# leddriver2X3.net
KiCad netlist of a schematic drawn in EAGLE
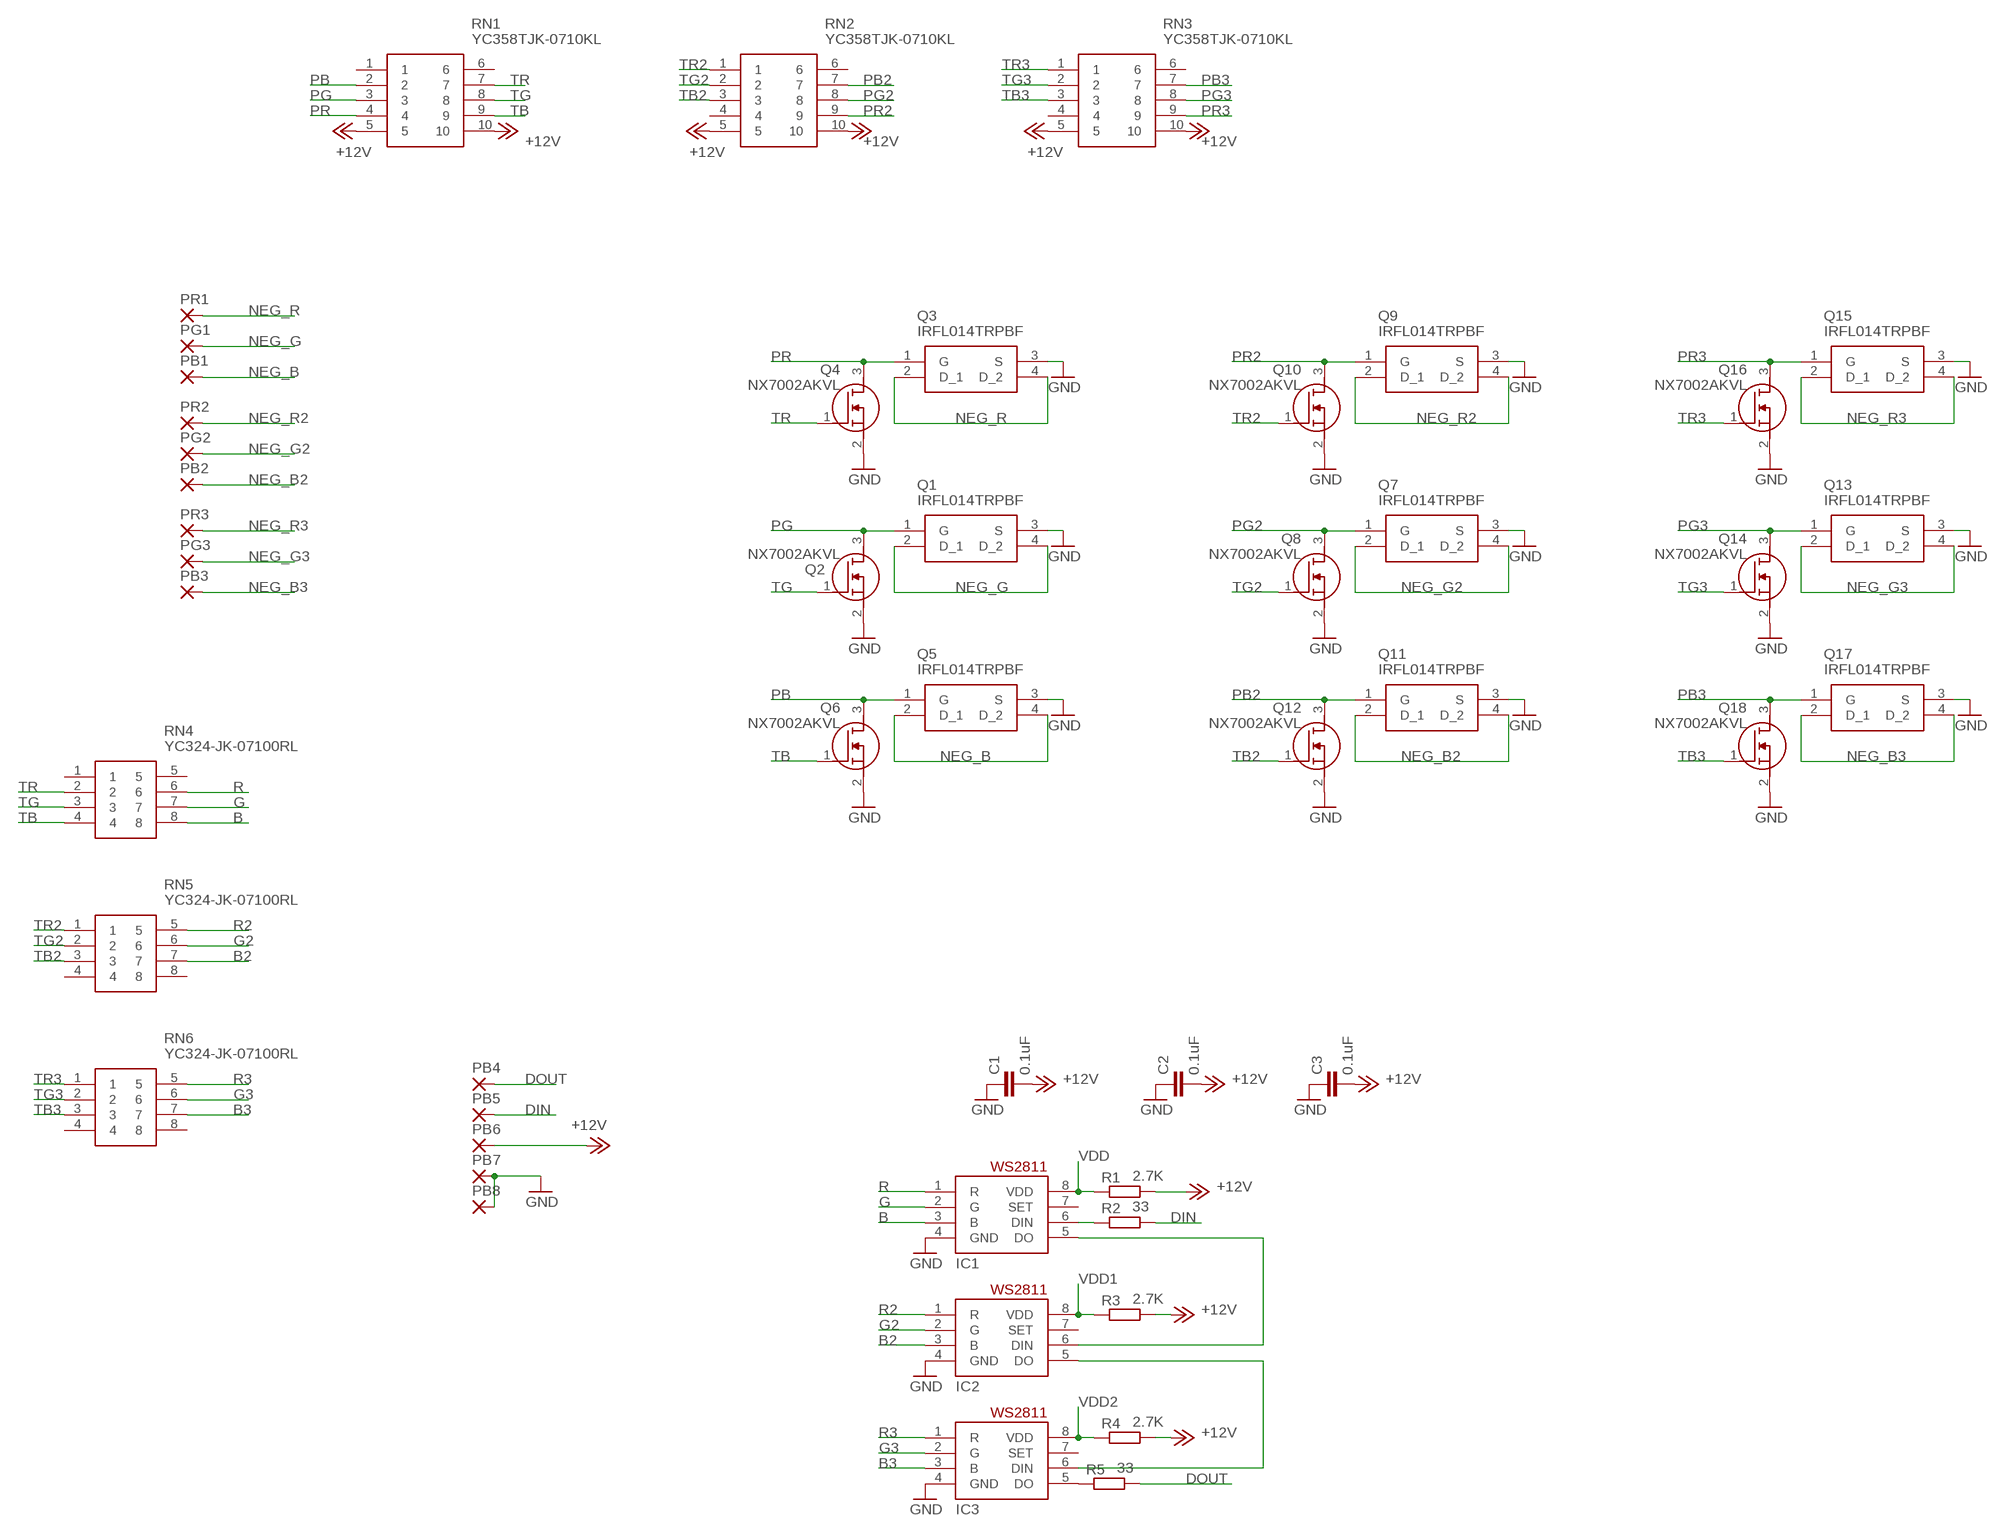
[diagram p0: schematic, sheet 1]

(export (version "E")
  (design (tool "Eeschema 10.0.6"))
  (components
    (comp (ref "C1")
      (value "0.1uF")
      (footprint "eagle-import:C1206")
      (libsource (lib "eagle-import") (part "C-EUC1206"))
    )
    (comp (ref "C2")
      (value "0.1uF")
      (footprint "eagle-import:C1206")
      (libsource (lib "eagle-import") (part "C-EUC1206"))
    )
    (comp (ref "C3")
      (value "0.1uF")
      (footprint "eagle-import:C1206")
      (libsource (lib "eagle-import") (part "C-EUC1206"))
    )
    (comp (ref "IC1")
      (value "WS2811-SOP8")
      (footprint "eagle-import:SO08-SKINNYPADS")
      (libsource (lib "eagle-import") (part "WS2811-SOP8"))
    )
    (comp (ref "IC2")
      (value "WS2811-SOP8")
      (footprint "eagle-import:SO08-SKINNYPADS")
      (libsource (lib "eagle-import") (part "WS2811-SOP8"))
    )
    (comp (ref "IC3")
      (value "WS2811-SOP8")
      (footprint "eagle-import:SO08-SKINNYPADS")
      (libsource (lib "eagle-import") (part "WS2811-SOP8"))
    )
    (comp (ref "PB1")
      (value "3,81/1,4")
      (footprint "eagle-import:3,81_1,4")
      (libsource (lib "eagle-import") (part "3,81/1,4"))
    )
    (comp (ref "PB2")
      (value "3,81/1,4")
      (footprint "eagle-import:3,81_1,4")
      (libsource (lib "eagle-import") (part "3,81/1,4"))
    )
    (comp (ref "PB3")
      (value "3,81/1,4")
      (footprint "eagle-import:3,81_1,4")
      (libsource (lib "eagle-import") (part "3,81/1,4"))
    )
    (comp (ref "PB4")
      (value "3,81/1,4")
      (footprint "eagle-import:3,81_1,4")
      (libsource (lib "eagle-import") (part "3,81/1,4"))
    )
    (comp (ref "PB5")
      (value "3,81/1,4")
      (footprint "eagle-import:3,81_1,4")
      (libsource (lib "eagle-import") (part "3,81/1,4"))
    )
    (comp (ref "PB6")
      (value "3,81/1,4")
      (footprint "eagle-import:3,81_1,4")
      (libsource (lib "eagle-import") (part "3,81/1,4"))
    )
    (comp (ref "PB7")
      (value "3,81/1,4")
      (footprint "eagle-import:3,81_1,4")
      (libsource (lib "eagle-import") (part "3,81/1,4"))
    )
    (comp (ref "PB8")
      (value "3,81/1,4")
      (footprint "eagle-import:3,81_1,4")
      (libsource (lib "eagle-import") (part "3,81/1,4"))
    )
    (comp (ref "PG1")
      (value "3,81/1,4")
      (footprint "eagle-import:3,81_1,4")
      (libsource (lib "eagle-import") (part "3,81/1,4"))
    )
    (comp (ref "PG2")
      (value "3,81/1,4")
      (footprint "eagle-import:3,81_1,4")
      (libsource (lib "eagle-import") (part "3,81/1,4"))
    )
    (comp (ref "PG3")
      (value "3,81/1,4")
      (footprint "eagle-import:3,81_1,4")
      (libsource (lib "eagle-import") (part "3,81/1,4"))
    )
    (comp (ref "PR1")
      (value "3,81/1,4")
      (footprint "eagle-import:3,81_1,4")
      (libsource (lib "eagle-import") (part "3,81/1,4"))
    )
    (comp (ref "PR2")
      (value "3,81/1,4")
      (footprint "eagle-import:3,81_1,4")
      (libsource (lib "eagle-import") (part "3,81/1,4"))
    )
    (comp (ref "PR3")
      (value "3,81/1,4")
      (footprint "eagle-import:3,81_1,4")
      (libsource (lib "eagle-import") (part "3,81/1,4"))
    )
    (comp (ref "Q1")
      (value "IRFL014TRPBF")
      (footprint "eagle-import:SOT230P700X180-4N")
      (fields (field (name "MOUSER_PART_NUMBER") "844-IRFL014TRPBF"))
      (libsource (lib "eagle-import") (part "IRFL014TRPBF"))
    )
    (comp (ref "Q2")
      (value "NX7002AKVL")
      (footprint "eagle-import:SOT95P230X110-3N")
      (fields (field (name "MOUSER_PART_NUMBER") "771-NX7002AKVL"))
      (libsource (lib "eagle-import") (part "NX7002AKVL"))
    )
    (comp (ref "Q3")
      (value "IRFL014TRPBF")
      (footprint "eagle-import:SOT230P700X180-4N")
      (fields (field (name "MOUSER_PART_NUMBER") "844-IRFL014TRPBF"))
      (libsource (lib "eagle-import") (part "IRFL014TRPBF"))
    )
    (comp (ref "Q4")
      (value "NX7002AKVL")
      (footprint "eagle-import:SOT95P230X110-3N")
      (fields (field (name "MOUSER_PART_NUMBER") "771-NX7002AKVL"))
      (libsource (lib "eagle-import") (part "NX7002AKVL"))
    )
    (comp (ref "Q5")
      (value "IRFL014TRPBF")
      (footprint "eagle-import:SOT230P700X180-4N")
      (fields (field (name "MOUSER_PART_NUMBER") "844-IRFL014TRPBF"))
      (libsource (lib "eagle-import") (part "IRFL014TRPBF"))
    )
    (comp (ref "Q6")
      (value "NX7002AKVL")
      (footprint "eagle-import:SOT95P230X110-3N")
      (fields (field (name "MOUSER_PART_NUMBER") "771-NX7002AKVL"))
      (libsource (lib "eagle-import") (part "NX7002AKVL"))
    )
    (comp (ref "Q7")
      (value "IRFL014TRPBF")
      (footprint "eagle-import:SOT230P700X180-4N")
      (fields (field (name "MOUSER_PART_NUMBER") "844-IRFL014TRPBF"))
      (libsource (lib "eagle-import") (part "IRFL014TRPBF"))
    )
    (comp (ref "Q8")
      (value "NX7002AKVL")
      (footprint "eagle-import:SOT95P230X110-3N")
      (fields (field (name "MOUSER_PART_NUMBER") "771-NX7002AKVL"))
      (libsource (lib "eagle-import") (part "NX7002AKVL"))
    )
    (comp (ref "Q9")
      (value "IRFL014TRPBF")
      (footprint "eagle-import:SOT230P700X180-4N")
      (fields (field (name "MOUSER_PART_NUMBER") "844-IRFL014TRPBF"))
      (libsource (lib "eagle-import") (part "IRFL014TRPBF"))
    )
    (comp (ref "Q10")
      (value "NX7002AKVL")
      (footprint "eagle-import:SOT95P230X110-3N")
      (fields (field (name "MOUSER_PART_NUMBER") "771-NX7002AKVL"))
      (libsource (lib "eagle-import") (part "NX7002AKVL"))
    )
    (comp (ref "Q11")
      (value "IRFL014TRPBF")
      (footprint "eagle-import:SOT230P700X180-4N")
      (fields (field (name "MOUSER_PART_NUMBER") "844-IRFL014TRPBF"))
      (libsource (lib "eagle-import") (part "IRFL014TRPBF"))
    )
    (comp (ref "Q12")
      (value "NX7002AKVL")
      (footprint "eagle-import:SOT95P230X110-3N")
      (fields (field (name "MOUSER_PART_NUMBER") "771-NX7002AKVL"))
      (libsource (lib "eagle-import") (part "NX7002AKVL"))
    )
    (comp (ref "Q13")
      (value "IRFL014TRPBF")
      (footprint "eagle-import:SOT230P700X180-4N")
      (fields (field (name "MOUSER_PART_NUMBER") "844-IRFL014TRPBF"))
      (libsource (lib "eagle-import") (part "IRFL014TRPBF"))
    )
    (comp (ref "Q14")
      (value "NX7002AKVL")
      (footprint "eagle-import:SOT95P230X110-3N")
      (fields (field (name "MOUSER_PART_NUMBER") "771-NX7002AKVL"))
      (libsource (lib "eagle-import") (part "NX7002AKVL"))
    )
    (comp (ref "Q15")
      (value "IRFL014TRPBF")
      (footprint "eagle-import:SOT230P700X180-4N")
      (fields (field (name "MOUSER_PART_NUMBER") "844-IRFL014TRPBF"))
      (libsource (lib "eagle-import") (part "IRFL014TRPBF"))
    )
    (comp (ref "Q16")
      (value "NX7002AKVL")
      (footprint "eagle-import:SOT95P230X110-3N")
      (fields (field (name "MOUSER_PART_NUMBER") "771-NX7002AKVL"))
      (libsource (lib "eagle-import") (part "NX7002AKVL"))
    )
    (comp (ref "Q17")
      (value "IRFL014TRPBF")
      (footprint "eagle-import:SOT230P700X180-4N")
      (fields (field (name "MOUSER_PART_NUMBER") "844-IRFL014TRPBF"))
      (libsource (lib "eagle-import") (part "IRFL014TRPBF"))
    )
    (comp (ref "Q18")
      (value "NX7002AKVL")
      (footprint "eagle-import:SOT95P230X110-3N")
      (fields (field (name "MOUSER_PART_NUMBER") "771-NX7002AKVL"))
      (libsource (lib "eagle-import") (part "NX7002AKVL"))
    )
    (comp (ref "R1")
      (value "2.7K")
      (footprint "eagle-import:R1206")
      (libsource (lib "eagle-import") (part "R-EU_R1206"))
    )
    (comp (ref "R2")
      (value "33")
      (footprint "eagle-import:R1206")
      (libsource (lib "eagle-import") (part "R-EU_R1206"))
    )
    (comp (ref "R3")
      (value "2.7K")
      (footprint "eagle-import:R1206")
      (libsource (lib "eagle-import") (part "R-EU_R1206"))
    )
    (comp (ref "R4")
      (value "2.7K")
      (footprint "eagle-import:R1206")
      (libsource (lib "eagle-import") (part "R-EU_R1206"))
    )
    (comp (ref "R5")
      (value "33")
      (footprint "eagle-import:R1206")
      (libsource (lib "eagle-import") (part "R-EU_R1206"))
    )
    (comp (ref "RN1")
      (value "YC358TJK-0710KL")
      (footprint "eagle-import:YC358T")
      (fields (field (name "MOUSER_PART_NUMBER") "603-YC358TJK-0710KL"))
      (libsource (lib "eagle-import") (part "YC358TJK-0710KL"))
    )
    (comp (ref "RN2")
      (value "YC358TJK-0710KL")
      (footprint "eagle-import:YC358T")
      (fields (field (name "MOUSER_PART_NUMBER") "603-YC358TJK-0710KL"))
      (libsource (lib "eagle-import") (part "YC358TJK-0710KL"))
    )
    (comp (ref "RN3")
      (value "YC358TJK-0710KL")
      (footprint "eagle-import:YC358T")
      (fields (field (name "MOUSER_PART_NUMBER") "603-YC358TJK-0710KL"))
      (libsource (lib "eagle-import") (part "YC358TJK-0710KL"))
    )
    (comp (ref "RN4")
      (value "YC324-JK-07100RL")
      (footprint "eagle-import:YC324JK07100RL")
      (fields (field (name "MOUSER_PART_NUMBER") "603-YC324-JK-07100RL"))
      (libsource (lib "eagle-import") (part "YC324-JK-07100RL"))
    )
    (comp (ref "RN5")
      (value "YC324-JK-07100RL")
      (footprint "eagle-import:YC324JK07100RL")
      (fields (field (name "MOUSER_PART_NUMBER") "603-YC324-JK-07100RL"))
      (libsource (lib "eagle-import") (part "YC324-JK-07100RL"))
    )
    (comp (ref "RN6")
      (value "YC324-JK-07100RL")
      (footprint "eagle-import:YC324JK07100RL")
      (fields (field (name "MOUSER_PART_NUMBER") "603-YC324-JK-07100RL"))
      (libsource (lib "eagle-import") (part "YC324-JK-07100RL"))
    )
  )
  (nets
    (net (code "1") (name "+12V") (class "Default")
      (node (ref "C1") (pin "2") (pinfunction "2_2") (pintype "passive"))
      (node (ref "C2") (pin "2") (pinfunction "2_2") (pintype "passive"))
      (node (ref "C3") (pin "2") (pinfunction "2_2") (pintype "passive"))
      (node (ref "PB6") (pin "1") (pinfunction "P_1") (pintype "passive"))
      (node (ref "R1") (pin "2") (pinfunction "2_2") (pintype "passive"))
      (node (ref "R3") (pin "2") (pinfunction "2_2") (pintype "passive"))
      (node (ref "R4") (pin "2") (pinfunction "2_2") (pintype "passive"))
      (node (ref "RN1") (pin "10") (pinfunction "10_10") (pintype "bidirectional"))
      (node (ref "RN1") (pin "5") (pinfunction "5_5") (pintype "bidirectional"))
      (node (ref "RN2") (pin "10") (pinfunction "10_10") (pintype "bidirectional"))
      (node (ref "RN2") (pin "5") (pinfunction "5_5") (pintype "bidirectional"))
      (node (ref "RN3") (pin "10") (pinfunction "10_10") (pintype "bidirectional"))
      (node (ref "RN3") (pin "5") (pinfunction "5_5") (pintype "bidirectional"))
    )
    (net (code "2") (name "/B") (class "Default")
      (node (ref "IC1") (pin "3") (pinfunction "B_3") (pintype "open_collector"))
      (node (ref "RN4") (pin "8") (pinfunction "8_8") (pintype "bidirectional"))
    )
    (net (code "3") (name "/B2") (class "Default")
      (node (ref "IC2") (pin "3") (pinfunction "B_3") (pintype "open_collector"))
      (node (ref "RN5") (pin "7") (pinfunction "7_7") (pintype "bidirectional"))
    )
    (net (code "4") (name "/B3") (class "Default")
      (node (ref "IC3") (pin "3") (pinfunction "B_3") (pintype "open_collector"))
      (node (ref "RN6") (pin "7") (pinfunction "7_7") (pintype "bidirectional"))
    )
    (net (code "5") (name "/DIN") (class "Default")
      (node (ref "PB5") (pin "1") (pinfunction "P_1") (pintype "passive"))
      (node (ref "R2") (pin "2") (pinfunction "2_2") (pintype "passive"))
    )
    (net (code "6") (name "/DOUT") (class "Default")
      (node (ref "PB4") (pin "1") (pinfunction "P_1") (pintype "passive"))
      (node (ref "R5") (pin "2") (pinfunction "2_2") (pintype "passive"))
    )
    (net (code "7") (name "/G") (class "Default")
      (node (ref "IC1") (pin "2") (pinfunction "G_2") (pintype "open_collector"))
      (node (ref "RN4") (pin "7") (pinfunction "7_7") (pintype "bidirectional"))
    )
    (net (code "8") (name "/G2") (class "Default")
      (node (ref "IC2") (pin "2") (pinfunction "G_2") (pintype "open_collector"))
      (node (ref "RN5") (pin "6") (pinfunction "6_6") (pintype "bidirectional"))
    )
    (net (code "9") (name "/G3") (class "Default")
      (node (ref "IC3") (pin "2") (pinfunction "G_2") (pintype "open_collector"))
      (node (ref "RN6") (pin "6") (pinfunction "6_6") (pintype "bidirectional"))
    )
    (net (code "10") (name "/NEG_B") (class "Default")
      (node (ref "PB1") (pin "1") (pinfunction "P_1") (pintype "passive"))
      (node (ref "Q5") (pin "2") (pinfunction "D_1_2") (pintype "bidirectional"))
      (node (ref "Q5") (pin "4") (pinfunction "D_2_4") (pintype "bidirectional"))
    )
    (net (code "11") (name "/NEG_B2") (class "Default")
      (node (ref "PB2") (pin "1") (pinfunction "P_1") (pintype "passive"))
      (node (ref "Q11") (pin "2") (pinfunction "D_1_2") (pintype "bidirectional"))
      (node (ref "Q11") (pin "4") (pinfunction "D_2_4") (pintype "bidirectional"))
    )
    (net (code "12") (name "/NEG_B3") (class "Default")
      (node (ref "PB3") (pin "1") (pinfunction "P_1") (pintype "passive"))
      (node (ref "Q17") (pin "2") (pinfunction "D_1_2") (pintype "bidirectional"))
      (node (ref "Q17") (pin "4") (pinfunction "D_2_4") (pintype "bidirectional"))
    )
    (net (code "13") (name "/NEG_G") (class "Default")
      (node (ref "PG1") (pin "1") (pinfunction "P_1") (pintype "passive"))
      (node (ref "Q1") (pin "2") (pinfunction "D_1_2") (pintype "bidirectional"))
      (node (ref "Q1") (pin "4") (pinfunction "D_2_4") (pintype "bidirectional"))
    )
    (net (code "14") (name "/NEG_G2") (class "Default")
      (node (ref "PG2") (pin "1") (pinfunction "P_1") (pintype "passive"))
      (node (ref "Q7") (pin "2") (pinfunction "D_1_2") (pintype "bidirectional"))
      (node (ref "Q7") (pin "4") (pinfunction "D_2_4") (pintype "bidirectional"))
    )
    (net (code "15") (name "/NEG_G3") (class "Default")
      (node (ref "PG3") (pin "1") (pinfunction "P_1") (pintype "passive"))
      (node (ref "Q13") (pin "2") (pinfunction "D_1_2") (pintype "bidirectional"))
      (node (ref "Q13") (pin "4") (pinfunction "D_2_4") (pintype "bidirectional"))
    )
    (net (code "16") (name "/NEG_R") (class "Default")
      (node (ref "PR1") (pin "1") (pinfunction "P_1") (pintype "passive"))
      (node (ref "Q3") (pin "2") (pinfunction "D_1_2") (pintype "bidirectional"))
      (node (ref "Q3") (pin "4") (pinfunction "D_2_4") (pintype "bidirectional"))
    )
    (net (code "17") (name "/NEG_R2") (class "Default")
      (node (ref "PR2") (pin "1") (pinfunction "P_1") (pintype "passive"))
      (node (ref "Q9") (pin "2") (pinfunction "D_1_2") (pintype "bidirectional"))
      (node (ref "Q9") (pin "4") (pinfunction "D_2_4") (pintype "bidirectional"))
    )
    (net (code "18") (name "/NEG_R3") (class "Default")
      (node (ref "PR3") (pin "1") (pinfunction "P_1") (pintype "passive"))
      (node (ref "Q15") (pin "2") (pinfunction "D_1_2") (pintype "bidirectional"))
      (node (ref "Q15") (pin "4") (pinfunction "D_2_4") (pintype "bidirectional"))
    )
    (net (code "19") (name "/PB") (class "Default")
      (node (ref "Q5") (pin "1") (pinfunction "G_1") (pintype "bidirectional"))
      (node (ref "Q6") (pin "3") (pinfunction "D_3") (pintype "bidirectional"))
      (node (ref "RN1") (pin "2") (pinfunction "2_2") (pintype "bidirectional"))
    )
    (net (code "20") (name "/PB2") (class "Default")
      (node (ref "Q11") (pin "1") (pinfunction "G_1") (pintype "bidirectional"))
      (node (ref "Q12") (pin "3") (pinfunction "D_3") (pintype "bidirectional"))
      (node (ref "RN2") (pin "7") (pinfunction "7_7") (pintype "bidirectional"))
    )
    (net (code "21") (name "/PB3") (class "Default")
      (node (ref "Q17") (pin "1") (pinfunction "G_1") (pintype "bidirectional"))
      (node (ref "Q18") (pin "3") (pinfunction "D_3") (pintype "bidirectional"))
      (node (ref "RN3") (pin "7") (pinfunction "7_7") (pintype "bidirectional"))
    )
    (net (code "22") (name "/PG") (class "Default")
      (node (ref "Q1") (pin "1") (pinfunction "G_1") (pintype "bidirectional"))
      (node (ref "Q2") (pin "3") (pinfunction "D_3") (pintype "bidirectional"))
      (node (ref "RN1") (pin "3") (pinfunction "3_3") (pintype "bidirectional"))
    )
    (net (code "23") (name "/PG2") (class "Default")
      (node (ref "Q7") (pin "1") (pinfunction "G_1") (pintype "bidirectional"))
      (node (ref "Q8") (pin "3") (pinfunction "D_3") (pintype "bidirectional"))
      (node (ref "RN2") (pin "8") (pinfunction "8_8") (pintype "bidirectional"))
    )
    (net (code "24") (name "/PG3") (class "Default")
      (node (ref "Q13") (pin "1") (pinfunction "G_1") (pintype "bidirectional"))
      (node (ref "Q14") (pin "3") (pinfunction "D_3") (pintype "bidirectional"))
      (node (ref "RN3") (pin "8") (pinfunction "8_8") (pintype "bidirectional"))
    )
    (net (code "25") (name "/PR") (class "Default")
      (node (ref "Q3") (pin "1") (pinfunction "G_1") (pintype "bidirectional"))
      (node (ref "Q4") (pin "3") (pinfunction "D_3") (pintype "bidirectional"))
      (node (ref "RN1") (pin "4") (pinfunction "4_4") (pintype "bidirectional"))
    )
    (net (code "26") (name "/PR2") (class "Default")
      (node (ref "Q10") (pin "3") (pinfunction "D_3") (pintype "bidirectional"))
      (node (ref "Q9") (pin "1") (pinfunction "G_1") (pintype "bidirectional"))
      (node (ref "RN2") (pin "9") (pinfunction "9_9") (pintype "bidirectional"))
    )
    (net (code "27") (name "/PR3") (class "Default")
      (node (ref "Q15") (pin "1") (pinfunction "G_1") (pintype "bidirectional"))
      (node (ref "Q16") (pin "3") (pinfunction "D_3") (pintype "bidirectional"))
      (node (ref "RN3") (pin "9") (pinfunction "9_9") (pintype "bidirectional"))
    )
    (net (code "28") (name "/R") (class "Default")
      (node (ref "IC1") (pin "1") (pinfunction "R_1") (pintype "open_collector"))
      (node (ref "RN4") (pin "6") (pinfunction "6_6") (pintype "bidirectional"))
    )
    (net (code "29") (name "/R2") (class "Default")
      (node (ref "IC2") (pin "1") (pinfunction "R_1") (pintype "open_collector"))
      (node (ref "RN5") (pin "5") (pinfunction "5_5") (pintype "bidirectional"))
    )
    (net (code "30") (name "/R3") (class "Default")
      (node (ref "IC3") (pin "1") (pinfunction "R_1") (pintype "open_collector"))
      (node (ref "RN6") (pin "5") (pinfunction "5_5") (pintype "bidirectional"))
    )
    (net (code "31") (name "/TB") (class "Default")
      (node (ref "Q6") (pin "1") (pinfunction "G_1") (pintype "bidirectional"))
      (node (ref "RN1") (pin "9") (pinfunction "9_9") (pintype "bidirectional"))
      (node (ref "RN4") (pin "4") (pinfunction "4_4") (pintype "bidirectional"))
    )
    (net (code "32") (name "/TB2") (class "Default")
      (node (ref "Q12") (pin "1") (pinfunction "G_1") (pintype "bidirectional"))
      (node (ref "RN2") (pin "3") (pinfunction "3_3") (pintype "bidirectional"))
      (node (ref "RN5") (pin "3") (pinfunction "3_3") (pintype "bidirectional"))
    )
    (net (code "33") (name "/TB3") (class "Default")
      (node (ref "Q18") (pin "1") (pinfunction "G_1") (pintype "bidirectional"))
      (node (ref "RN3") (pin "3") (pinfunction "3_3") (pintype "bidirectional"))
      (node (ref "RN6") (pin "3") (pinfunction "3_3") (pintype "bidirectional"))
    )
    (net (code "34") (name "/TG") (class "Default")
      (node (ref "Q2") (pin "1") (pinfunction "G_1") (pintype "bidirectional"))
      (node (ref "RN1") (pin "8") (pinfunction "8_8") (pintype "bidirectional"))
      (node (ref "RN4") (pin "3") (pinfunction "3_3") (pintype "bidirectional"))
    )
    (net (code "35") (name "/TG2") (class "Default")
      (node (ref "Q8") (pin "1") (pinfunction "G_1") (pintype "bidirectional"))
      (node (ref "RN2") (pin "2") (pinfunction "2_2") (pintype "bidirectional"))
      (node (ref "RN5") (pin "2") (pinfunction "2_2") (pintype "bidirectional"))
    )
    (net (code "36") (name "/TG3") (class "Default")
      (node (ref "Q14") (pin "1") (pinfunction "G_1") (pintype "bidirectional"))
      (node (ref "RN3") (pin "2") (pinfunction "2_2") (pintype "bidirectional"))
      (node (ref "RN6") (pin "2") (pinfunction "2_2") (pintype "bidirectional"))
    )
    (net (code "37") (name "/TR") (class "Default")
      (node (ref "Q4") (pin "1") (pinfunction "G_1") (pintype "bidirectional"))
      (node (ref "RN1") (pin "7") (pinfunction "7_7") (pintype "bidirectional"))
      (node (ref "RN4") (pin "2") (pinfunction "2_2") (pintype "bidirectional"))
    )
    (net (code "38") (name "/TR2") (class "Default")
      (node (ref "Q10") (pin "1") (pinfunction "G_1") (pintype "bidirectional"))
      (node (ref "RN2") (pin "1") (pinfunction "1_1") (pintype "bidirectional"))
      (node (ref "RN5") (pin "1") (pinfunction "1_1") (pintype "bidirectional"))
    )
    (net (code "39") (name "/TR3") (class "Default")
      (node (ref "Q16") (pin "1") (pinfunction "G_1") (pintype "bidirectional"))
      (node (ref "RN3") (pin "1") (pinfunction "1_1") (pintype "bidirectional"))
      (node (ref "RN6") (pin "1") (pinfunction "1_1") (pintype "bidirectional"))
    )
    (net (code "40") (name "/VDD") (class "Default")
      (node (ref "IC1") (pin "8") (pinfunction "VDD_8") (pintype "power_in"))
      (node (ref "R1") (pin "1") (pinfunction "1_1") (pintype "passive"))
    )
    (net (code "41") (name "/VDD1") (class "Default")
      (node (ref "IC2") (pin "8") (pinfunction "VDD_8") (pintype "power_in"))
      (node (ref "R3") (pin "1") (pinfunction "1_1") (pintype "passive"))
    )
    (net (code "42") (name "/VDD2") (class "Default")
      (node (ref "IC3") (pin "8") (pinfunction "VDD_8") (pintype "power_in"))
      (node (ref "R4") (pin "1") (pinfunction "1_1") (pintype "passive"))
    )
    (net (code "43") (name "GND") (class "Default")
      (node (ref "C1") (pin "1") (pinfunction "1_1") (pintype "passive"))
      (node (ref "C2") (pin "1") (pinfunction "1_1") (pintype "passive"))
      (node (ref "C3") (pin "1") (pinfunction "1_1") (pintype "passive"))
      (node (ref "IC1") (pin "4") (pinfunction "GND_4") (pintype "power_in"))
      (node (ref "IC2") (pin "4") (pinfunction "GND_4") (pintype "power_in"))
      (node (ref "IC3") (pin "4") (pinfunction "GND_4") (pintype "power_in"))
      (node (ref "PB7") (pin "1") (pinfunction "P_1") (pintype "passive"))
      (node (ref "PB8") (pin "1") (pinfunction "P_1") (pintype "passive"))
      (node (ref "Q1") (pin "3") (pinfunction "S_3") (pintype "bidirectional"))
      (node (ref "Q10") (pin "2") (pinfunction "S_2") (pintype "bidirectional"))
      (node (ref "Q11") (pin "3") (pinfunction "S_3") (pintype "bidirectional"))
      (node (ref "Q12") (pin "2") (pinfunction "S_2") (pintype "bidirectional"))
      (node (ref "Q13") (pin "3") (pinfunction "S_3") (pintype "bidirectional"))
      (node (ref "Q14") (pin "2") (pinfunction "S_2") (pintype "bidirectional"))
      (node (ref "Q15") (pin "3") (pinfunction "S_3") (pintype "bidirectional"))
      (node (ref "Q16") (pin "2") (pinfunction "S_2") (pintype "bidirectional"))
      (node (ref "Q17") (pin "3") (pinfunction "S_3") (pintype "bidirectional"))
      (node (ref "Q18") (pin "2") (pinfunction "S_2") (pintype "bidirectional"))
      (node (ref "Q2") (pin "2") (pinfunction "S_2") (pintype "bidirectional"))
      (node (ref "Q3") (pin "3") (pinfunction "S_3") (pintype "bidirectional"))
      (node (ref "Q4") (pin "2") (pinfunction "S_2") (pintype "bidirectional"))
      (node (ref "Q5") (pin "3") (pinfunction "S_3") (pintype "bidirectional"))
      (node (ref "Q6") (pin "2") (pinfunction "S_2") (pintype "bidirectional"))
      (node (ref "Q7") (pin "3") (pinfunction "S_3") (pintype "bidirectional"))
      (node (ref "Q8") (pin "2") (pinfunction "S_2") (pintype "bidirectional"))
      (node (ref "Q9") (pin "3") (pinfunction "S_3") (pintype "bidirectional"))
    )
    (net (code "44") (name "Net-(IC1-DIN)") (class "Default")
      (node (ref "IC1") (pin "6") (pinfunction "DIN_6") (pintype "input"))
      (node (ref "R2") (pin "1") (pinfunction "1_1") (pintype "passive"))
    )
    (net (code "45") (name "Net-(IC1-DO)") (class "Default")
      (node (ref "IC1") (pin "5") (pinfunction "DO_5") (pintype "output"))
      (node (ref "IC2") (pin "6") (pinfunction "DIN_6") (pintype "input"))
    )
    (net (code "46") (name "Net-(IC2-DO)") (class "Default")
      (node (ref "IC2") (pin "5") (pinfunction "DO_5") (pintype "output"))
      (node (ref "IC3") (pin "6") (pinfunction "DIN_6") (pintype "input"))
    )
    (net (code "47") (name "Net-(IC3-DO)") (class "Default")
      (node (ref "IC3") (pin "5") (pinfunction "DO_5") (pintype "output"))
      (node (ref "R5") (pin "1") (pinfunction "1_1") (pintype "passive"))
    )
    (net (code "48") (name "unconnected-(IC1-SET-Pad7)") (class "Default")
      (node (ref "IC1") (pin "7") (pinfunction "SET_7") (pintype "input"))
    )
    (net (code "49") (name "unconnected-(IC2-SET-Pad7)") (class "Default")
      (node (ref "IC2") (pin "7") (pinfunction "SET_7") (pintype "input"))
    )
    (net (code "50") (name "unconnected-(IC3-SET-Pad7)") (class "Default")
      (node (ref "IC3") (pin "7") (pinfunction "SET_7") (pintype "input"))
    )
    (net (code "51") (name "unconnected-(RN1-Pad1)") (class "Default")
      (node (ref "RN1") (pin "1") (pinfunction "1_1") (pintype "bidirectional"))
    )
    (net (code "52") (name "unconnected-(RN1-Pad6)") (class "Default")
      (node (ref "RN1") (pin "6") (pinfunction "6_6") (pintype "bidirectional"))
    )
    (net (code "53") (name "unconnected-(RN2-Pad4)") (class "Default")
      (node (ref "RN2") (pin "4") (pinfunction "4_4") (pintype "bidirectional"))
    )
    (net (code "54") (name "unconnected-(RN2-Pad6)") (class "Default")
      (node (ref "RN2") (pin "6") (pinfunction "6_6") (pintype "bidirectional"))
    )
    (net (code "55") (name "unconnected-(RN3-Pad4)") (class "Default")
      (node (ref "RN3") (pin "4") (pinfunction "4_4") (pintype "bidirectional"))
    )
    (net (code "56") (name "unconnected-(RN3-Pad6)") (class "Default")
      (node (ref "RN3") (pin "6") (pinfunction "6_6") (pintype "bidirectional"))
    )
    (net (code "57") (name "unconnected-(RN4-Pad1)") (class "Default")
      (node (ref "RN4") (pin "1") (pinfunction "1_1") (pintype "bidirectional"))
    )
    (net (code "58") (name "unconnected-(RN4-Pad5)") (class "Default")
      (node (ref "RN4") (pin "5") (pinfunction "5_5") (pintype "bidirectional"))
    )
    (net (code "59") (name "unconnected-(RN5-Pad4)") (class "Default")
      (node (ref "RN5") (pin "4") (pinfunction "4_4") (pintype "bidirectional"))
    )
    (net (code "60") (name "unconnected-(RN5-Pad8)") (class "Default")
      (node (ref "RN5") (pin "8") (pinfunction "8_8") (pintype "bidirectional"))
    )
    (net (code "61") (name "unconnected-(RN6-Pad4)") (class "Default")
      (node (ref "RN6") (pin "4") (pinfunction "4_4") (pintype "bidirectional"))
    )
    (net (code "62") (name "unconnected-(RN6-Pad8)") (class "Default")
      (node (ref "RN6") (pin "8") (pinfunction "8_8") (pintype "bidirectional"))
    )
  )
)
